# MCU.net
KiCad netlist of a schematic drawn in Altium Designer
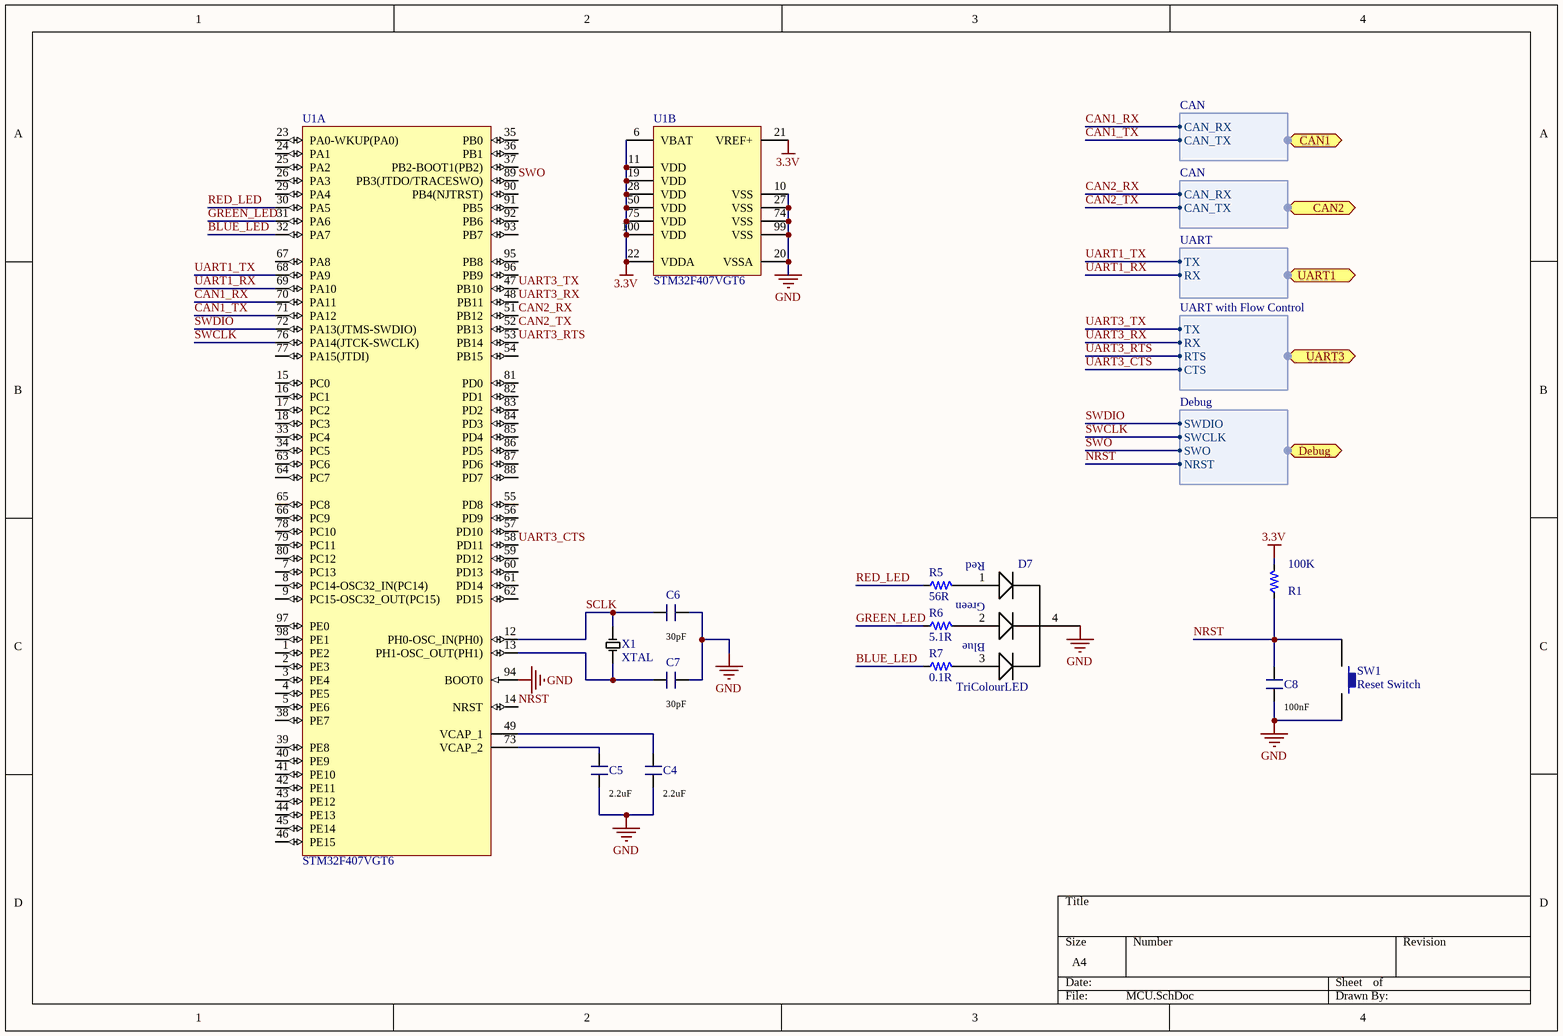
[diagram p0: MCU.SchDoc]

(export (version "E")
  (design (tool "Eeschema 10.0.6"))
  (components
    (comp (ref "C4")
      (value "SCH_GENERIC_CAPACITOR_0603")
      (footprint "PCB_GENERIC_SMD_0603")
      (description "Generic SMD capacitor 0603")
      (fields (field (name "TOLERANCE") "*%") (field (name "CAPACITANCE") "2.2uF"))
      (libsource (lib "Capacitors") (part "SCH_GENERIC_CAPACITOR_0603"))
    )
    (comp (ref "C5")
      (value "SCH_GENERIC_CAPACITOR_0603")
      (footprint "PCB_GENERIC_SMD_0603")
      (description "Generic SMD capacitor 0603")
      (fields (field (name "TOLERANCE") "*%") (field (name "CAPACITANCE") "2.2uF"))
      (libsource (lib "Capacitors") (part "SCH_GENERIC_CAPACITOR_0603"))
    )
    (comp (ref "C6")
      (value "SCH_GENERIC_CAPACITOR_0603")
      (footprint "PCB_GENERIC_SMD_0603")
      (description "Generic SMD capacitor 0603")
      (fields (field (name "TOLERANCE") "*%") (field (name "CAPACITANCE") "30pF"))
      (libsource (lib "Capacitors") (part "SCH_GENERIC_CAPACITOR_0603"))
    )
    (comp (ref "C7")
      (value "SCH_GENERIC_CAPACITOR_0603")
      (footprint "PCB_GENERIC_SMD_0603")
      (description "Generic SMD capacitor 0603")
      (fields (field (name "TOLERANCE") "*%") (field (name "CAPACITANCE") "30pF"))
      (libsource (lib "Capacitors") (part "SCH_GENERIC_CAPACITOR_0603"))
    )
    (comp (ref "C8")
      (value "SCH_GENERIC_CAPACITOR_0603")
      (footprint "PCB_GENERIC_SMD_0603")
      (description "Generic SMD capacitor 0603")
      (fields (field (name "TOLERANCE") "*%") (field (name "CAPACITANCE") "100nF"))
      (libsource (lib "Capacitors") (part "SCH_GENERIC_CAPACITOR_0603"))
    )
    (comp (ref "D7")
      (value "TriColourLED")
      (footprint "TricolourLED - SunLED - DK  1497-1225-2-ND")
      (libsource (lib "TricolourLED - SunLED - DK 1497-1225-2-ND") (part "TriColourLED"))
    )
    (comp (ref "R1")
      (value "SCH_GENERIC_RESISTOR_0603")
      (footprint "PCB_GENERIC_SMD_0603")
      (description "Generic SMD resistor 0603")
      (fields (field (name "RESISTANCE") "100K"))
      (libsource (lib "Resistors") (part "SCH_GENERIC_RESISTOR_0603"))
    )
    (comp (ref "R5")
      (value "SCH_GENERIC_RESISTOR_0603")
      (footprint "PCB_GENERIC_SMD_0603")
      (description "Generic SMD resistor 0603")
      (fields (field (name "RESISTANCE") "56R"))
      (libsource (lib "SCH_GENERIC_RESISTOR_0603") (part "SCH_GENERIC_RESISTOR_0603"))
    )
    (comp (ref "R6")
      (value "SCH_GENERIC_RESISTOR_0603")
      (footprint "PCB_GENERIC_SMD_0603")
      (description "Generic SMD resistor 0603")
      (fields (field (name "RESISTANCE") "5.1R"))
      (libsource (lib "SCH_GENERIC_RESISTOR_0603") (part "SCH_GENERIC_RESISTOR_0603"))
    )
    (comp (ref "R7")
      (value "SCH_GENERIC_RESISTOR_0603")
      (footprint "PCB_GENERIC_SMD_0603")
      (description "Generic SMD resistor 0603")
      (fields (field (name "RESISTANCE") "0.1R"))
      (libsource (lib "SCH_GENERIC_RESISTOR_0603") (part "SCH_GENERIC_RESISTOR_0603"))
    )
    (comp (ref "SW1")
      (value "Reset Switch")
      (footprint "Push Button Switch")
      (libsource (lib "PushButtonSwitch") (part "PushButtonSwitch"))
    )
    (comp (ref "U1")
      (value "STM32F407VGT6")
      (footprint "STM-LQFP100_N")
      (fields (field (name "MANUFACTURER") "STMicroelectronics"))
      (libsource (lib "STMicroelectronics STM32 F4") (part "STM32F407VGT6"))
    )
    (comp (ref "X1") (value "XTAL") (footprint "CRYSTAL_8MHZ") (libsource (lib "Crystal") (part "Crystal")))
  )
  (nets
    (net (code "7") (name "/BLUE_LED") (class "Default")
      (node (ref "R7") (pin "1") (pinfunction "1_1") (pintype "passive"))
      (node (ref "U1") (pin "32") (pinfunction "PA7_32") (pintype "bidirectional"))
    )
    (net (code "8") (name "/CAN1_RX") (class "Default")
      (node (ref "U1") (pin "70") (pinfunction "PA11_70") (pintype "bidirectional"))
    )
    (net (code "9") (name "/CAN1_TX") (class "Default")
      (node (ref "U1") (pin "71") (pinfunction "PA12_71") (pintype "bidirectional"))
    )
    (net (code "10") (name "/CAN2_RX") (class "Default")
      (node (ref "U1") (pin "51") (pinfunction "PB12_51") (pintype "bidirectional"))
    )
    (net (code "11") (name "/CAN2_TX") (class "Default")
      (node (ref "U1") (pin "52") (pinfunction "PB13_52") (pintype "bidirectional"))
    )
    (net (code "12") (name "/GREEN_LED") (class "Default")
      (node (ref "R6") (pin "1") (pinfunction "1_1") (pintype "passive"))
      (node (ref "U1") (pin "31") (pinfunction "PA6_31") (pintype "bidirectional"))
    )
    (net (code "13") (name "/NRST") (class "Default")
      (node (ref "C8") (pin "1") (pinfunction "1_1") (pintype "passive"))
      (node (ref "R1") (pin "1") (pinfunction "1_1") (pintype "passive"))
      (node (ref "SW1") (pin "1") (pinfunction "1_1") (pintype "passive"))
      (node (ref "U1") (pin "14") (pinfunction "NRST_14") (pintype "bidirectional"))
    )
    (net (code "14") (name "/RED_LED") (class "Default")
      (node (ref "R5") (pin "1") (pinfunction "1_1") (pintype "passive"))
      (node (ref "U1") (pin "30") (pinfunction "PA5_30") (pintype "bidirectional"))
    )
    (net (code "15") (name "/SCLK") (class "Default")
      (node (ref "C6") (pin "2") (pinfunction "2_2") (pintype "passive"))
      (node (ref "U1") (pin "12") (pinfunction "PH0-OSC_IN(PH0)_12") (pintype "bidirectional"))
      (node (ref "X1") (pin "1") (pintype "passive"))
    )
    (net (code "16") (name "/SWCLK") (class "Default")
      (node (ref "U1") (pin "76") (pinfunction "PA14(JTCK-SWCLK)_76") (pintype "bidirectional"))
    )
    (net (code "17") (name "/SWDIO") (class "Default")
      (node (ref "U1") (pin "72") (pinfunction "PA13(JTMS-SWDIO)_72") (pintype "bidirectional"))
    )
    (net (code "18") (name "/SWO") (class "Default")
      (node (ref "U1") (pin "89") (pinfunction "PB3(JTDO/TRACESWO)_89") (pintype "bidirectional"))
    )
    (net (code "19") (name "/UART1_RX") (class "Default")
      (node (ref "U1") (pin "69") (pinfunction "PA10_69") (pintype "bidirectional"))
    )
    (net (code "20") (name "/UART1_TX") (class "Default")
      (node (ref "U1") (pin "68") (pinfunction "PA9_68") (pintype "bidirectional"))
    )
    (net (code "21") (name "/UART3_CTS") (class "Default")
      (node (ref "U1") (pin "58") (pinfunction "PD11_58") (pintype "bidirectional"))
    )
    (net (code "22") (name "/UART3_RTS") (class "Default")
      (node (ref "U1") (pin "53") (pinfunction "PB14_53") (pintype "bidirectional"))
    )
    (net (code "23") (name "/UART3_RX") (class "Default")
      (node (ref "U1") (pin "48") (pinfunction "PB11_48") (pintype "bidirectional"))
    )
    (net (code "24") (name "/UART3_TX") (class "Default")
      (node (ref "U1") (pin "47") (pinfunction "PB10_47") (pintype "bidirectional"))
    )
    (net (code "29") (name "3.3V") (class "Default")
      (node (ref "R1") (pin "2") (pinfunction "2_2") (pintype "passive"))
      (node (ref "U1") (pin "100") (pinfunction "VDD_100") (pintype "power_in"))
      (node (ref "U1") (pin "11") (pinfunction "VDD_11") (pintype "power_in"))
      (node (ref "U1") (pin "19") (pinfunction "VDD_19") (pintype "power_in"))
      (node (ref "U1") (pin "21") (pinfunction "VREF+_21") (pintype "power_in"))
      (node (ref "U1") (pin "22") (pinfunction "VDDA_22") (pintype "power_in"))
      (node (ref "U1") (pin "28") (pinfunction "VDD_28") (pintype "power_in"))
      (node (ref "U1") (pin "50") (pinfunction "VDD_50") (pintype "power_in"))
      (node (ref "U1") (pin "6") (pinfunction "VBAT_6") (pintype "power_in"))
      (node (ref "U1") (pin "75") (pinfunction "VDD_75") (pintype "power_in"))
    )
    (net (code "30") (name "GND") (class "Default")
      (node (ref "C4") (pin "1") (pinfunction "1_1") (pintype "passive"))
      (node (ref "C5") (pin "1") (pinfunction "1_1") (pintype "passive"))
      (node (ref "C6") (pin "1") (pinfunction "1_1") (pintype "passive"))
      (node (ref "C7") (pin "1") (pinfunction "1_1") (pintype "passive"))
      (node (ref "C8") (pin "2") (pinfunction "2_2") (pintype "passive"))
      (node (ref "D7") (pin "4") (pinfunction "4_4") (pintype "passive"))
      (node (ref "SW1") (pin "2") (pinfunction "2_2") (pintype "passive"))
      (node (ref "U1") (pin "10") (pinfunction "VSS_10") (pintype "power_in"))
      (node (ref "U1") (pin "20") (pinfunction "VSSA_20") (pintype "power_in"))
      (node (ref "U1") (pin "27") (pinfunction "VSS_27") (pintype "power_in"))
      (node (ref "U1") (pin "74") (pinfunction "VSS_74") (pintype "power_in"))
      (node (ref "U1") (pin "94") (pinfunction "BOOT0_94") (pintype "input"))
      (node (ref "U1") (pin "99") (pinfunction "VSS_99") (pintype "power_in"))
    )
    (net (code "31") (name "Net-(D7-Blue)") (class "Default")
      (node (ref "D7") (pin "3") (pinfunction "Blue_3") (pintype "passive"))
      (node (ref "R7") (pin "2") (pinfunction "2_2") (pintype "passive"))
    )
    (net (code "32") (name "Net-(D7-Green)") (class "Default")
      (node (ref "D7") (pin "2") (pinfunction "Green_2") (pintype "passive"))
      (node (ref "R6") (pin "2") (pinfunction "2_2") (pintype "passive"))
    )
    (net (code "33") (name "Net-(D7-Red)") (class "Default")
      (node (ref "D7") (pin "1") (pinfunction "Red_1") (pintype "passive"))
      (node (ref "R5") (pin "2") (pinfunction "2_2") (pintype "passive"))
    )
    (net (code "34") (name "Net-(U1A-PH1-OSC_OUT(PH1))") (class "Default")
      (node (ref "C7") (pin "2") (pinfunction "2_2") (pintype "passive"))
      (node (ref "U1") (pin "13") (pinfunction "PH1-OSC_OUT(PH1)_13") (pintype "bidirectional"))
      (node (ref "X1") (pin "2") (pintype "passive"))
    )
    (net (code "35") (name "Net-(U1A-VCAP_1)") (class "Default")
      (node (ref "C4") (pin "2") (pinfunction "2_2") (pintype "passive"))
      (node (ref "U1") (pin "49") (pinfunction "VCAP_1_49") (pintype "power_in"))
    )
    (net (code "36") (name "Net-(U1A-VCAP_2)") (class "Default")
      (node (ref "C5") (pin "2") (pinfunction "2_2") (pintype "passive"))
      (node (ref "U1") (pin "73") (pinfunction "VCAP_2_73") (pintype "power_in"))
    )
    (net (code "37") (name "unconnected-(U1A-PA0-WKUP(PA0)-Pad23)") (class "Default")
      (node (ref "U1") (pin "23") (pinfunction "PA0-WKUP(PA0)_23") (pintype "bidirectional"))
    )
    (net (code "38") (name "unconnected-(U1A-PA1-Pad24)") (class "Default")
      (node (ref "U1") (pin "24") (pinfunction "PA1_24") (pintype "bidirectional"))
    )
    (net (code "39") (name "unconnected-(U1A-PA2-Pad25)") (class "Default")
      (node (ref "U1") (pin "25") (pinfunction "PA2_25") (pintype "bidirectional"))
    )
    (net (code "40") (name "unconnected-(U1A-PA3-Pad26)") (class "Default")
      (node (ref "U1") (pin "26") (pinfunction "PA3_26") (pintype "bidirectional"))
    )
    (net (code "41") (name "unconnected-(U1A-PA4-Pad29)") (class "Default")
      (node (ref "U1") (pin "29") (pinfunction "PA4_29") (pintype "bidirectional"))
    )
    (net (code "42") (name "unconnected-(U1A-PA8-Pad67)") (class "Default")
      (node (ref "U1") (pin "67") (pinfunction "PA8_67") (pintype "bidirectional"))
    )
    (net (code "43") (name "unconnected-(U1A-PA15(JTDI)-Pad77)") (class "Default")
      (node (ref "U1") (pin "77") (pinfunction "PA15(JTDI)_77") (pintype "bidirectional"))
    )
    (net (code "44") (name "unconnected-(U1A-PB0-Pad35)") (class "Default")
      (node (ref "U1") (pin "35") (pinfunction "PB0_35") (pintype "bidirectional"))
    )
    (net (code "45") (name "unconnected-(U1A-PB1-Pad36)") (class "Default")
      (node (ref "U1") (pin "36") (pinfunction "PB1_36") (pintype "bidirectional"))
    )
    (net (code "46") (name "unconnected-(U1A-PB2-BOOT1(PB2)-Pad37)") (class "Default")
      (node (ref "U1") (pin "37") (pinfunction "PB2-BOOT1(PB2)_37") (pintype "bidirectional"))
    )
    (net (code "47") (name "unconnected-(U1A-PB4(NJTRST)-Pad90)") (class "Default")
      (node (ref "U1") (pin "90") (pinfunction "PB4(NJTRST)_90") (pintype "bidirectional"))
    )
    (net (code "48") (name "unconnected-(U1A-PB5-Pad91)") (class "Default")
      (node (ref "U1") (pin "91") (pinfunction "PB5_91") (pintype "bidirectional"))
    )
    (net (code "49") (name "unconnected-(U1A-PB6-Pad92)") (class "Default")
      (node (ref "U1") (pin "92") (pinfunction "PB6_92") (pintype "bidirectional"))
    )
    (net (code "50") (name "unconnected-(U1A-PB7-Pad93)") (class "Default")
      (node (ref "U1") (pin "93") (pinfunction "PB7_93") (pintype "bidirectional"))
    )
    (net (code "51") (name "unconnected-(U1A-PB8-Pad95)") (class "Default")
      (node (ref "U1") (pin "95") (pinfunction "PB8_95") (pintype "bidirectional"))
    )
    (net (code "52") (name "unconnected-(U1A-PB9-Pad96)") (class "Default")
      (node (ref "U1") (pin "96") (pinfunction "PB9_96") (pintype "bidirectional"))
    )
    (net (code "53") (name "unconnected-(U1A-PB15-Pad54)") (class "Default")
      (node (ref "U1") (pin "54") (pinfunction "PB15_54") (pintype "bidirectional"))
    )
    (net (code "54") (name "unconnected-(U1A-PC0-Pad15)") (class "Default")
      (node (ref "U1") (pin "15") (pinfunction "PC0_15") (pintype "bidirectional"))
    )
    (net (code "55") (name "unconnected-(U1A-PC1-Pad16)") (class "Default")
      (node (ref "U1") (pin "16") (pinfunction "PC1_16") (pintype "bidirectional"))
    )
    (net (code "56") (name "unconnected-(U1A-PC2-Pad17)") (class "Default")
      (node (ref "U1") (pin "17") (pinfunction "PC2_17") (pintype "bidirectional"))
    )
    (net (code "57") (name "unconnected-(U1A-PC3-Pad18)") (class "Default")
      (node (ref "U1") (pin "18") (pinfunction "PC3_18") (pintype "bidirectional"))
    )
    (net (code "58") (name "unconnected-(U1A-PC4-Pad33)") (class "Default")
      (node (ref "U1") (pin "33") (pinfunction "PC4_33") (pintype "bidirectional"))
    )
    (net (code "59") (name "unconnected-(U1A-PC5-Pad34)") (class "Default")
      (node (ref "U1") (pin "34") (pinfunction "PC5_34") (pintype "bidirectional"))
    )
    (net (code "60") (name "unconnected-(U1A-PC6-Pad63)") (class "Default")
      (node (ref "U1") (pin "63") (pinfunction "PC6_63") (pintype "bidirectional"))
    )
    (net (code "61") (name "unconnected-(U1A-PC7-Pad64)") (class "Default")
      (node (ref "U1") (pin "64") (pinfunction "PC7_64") (pintype "bidirectional"))
    )
    (net (code "62") (name "unconnected-(U1A-PC8-Pad65)") (class "Default")
      (node (ref "U1") (pin "65") (pinfunction "PC8_65") (pintype "bidirectional"))
    )
    (net (code "63") (name "unconnected-(U1A-PC9-Pad66)") (class "Default")
      (node (ref "U1") (pin "66") (pinfunction "PC9_66") (pintype "bidirectional"))
    )
    (net (code "64") (name "unconnected-(U1A-PC10-Pad78)") (class "Default")
      (node (ref "U1") (pin "78") (pinfunction "PC10_78") (pintype "bidirectional"))
    )
    (net (code "65") (name "unconnected-(U1A-PC11-Pad79)") (class "Default")
      (node (ref "U1") (pin "79") (pinfunction "PC11_79") (pintype "bidirectional"))
    )
    (net (code "66") (name "unconnected-(U1A-PC12-Pad80)") (class "Default")
      (node (ref "U1") (pin "80") (pinfunction "PC12_80") (pintype "bidirectional"))
    )
    (net (code "67") (name "unconnected-(U1A-PC13-Pad7)") (class "Default")
      (node (ref "U1") (pin "7") (pinfunction "PC13_7") (pintype "bidirectional"))
    )
    (net (code "68") (name "unconnected-(U1A-PC14-OSC32_IN(PC14)-Pad8)") (class "Default")
      (node (ref "U1") (pin "8") (pinfunction "PC14-OSC32_IN(PC14)_8") (pintype "bidirectional"))
    )
    (net (code "69") (name "unconnected-(U1A-PC15-OSC32_OUT(PC15)-Pad9)") (class "Default")
      (node (ref "U1") (pin "9") (pinfunction "PC15-OSC32_OUT(PC15)_9") (pintype "bidirectional"))
    )
    (net (code "70") (name "unconnected-(U1A-PD0-Pad81)") (class "Default")
      (node (ref "U1") (pin "81") (pinfunction "PD0_81") (pintype "bidirectional"))
    )
    (net (code "71") (name "unconnected-(U1A-PD1-Pad82)") (class "Default")
      (node (ref "U1") (pin "82") (pinfunction "PD1_82") (pintype "bidirectional"))
    )
    (net (code "72") (name "unconnected-(U1A-PD2-Pad83)") (class "Default")
      (node (ref "U1") (pin "83") (pinfunction "PD2_83") (pintype "bidirectional"))
    )
    (net (code "73") (name "unconnected-(U1A-PD3-Pad84)") (class "Default")
      (node (ref "U1") (pin "84") (pinfunction "PD3_84") (pintype "bidirectional"))
    )
    (net (code "74") (name "unconnected-(U1A-PD4-Pad85)") (class "Default")
      (node (ref "U1") (pin "85") (pinfunction "PD4_85") (pintype "bidirectional"))
    )
    (net (code "75") (name "unconnected-(U1A-PD5-Pad86)") (class "Default")
      (node (ref "U1") (pin "86") (pinfunction "PD5_86") (pintype "bidirectional"))
    )
    (net (code "76") (name "unconnected-(U1A-PD6-Pad87)") (class "Default")
      (node (ref "U1") (pin "87") (pinfunction "PD6_87") (pintype "bidirectional"))
    )
    (net (code "77") (name "unconnected-(U1A-PD7-Pad88)") (class "Default")
      (node (ref "U1") (pin "88") (pinfunction "PD7_88") (pintype "bidirectional"))
    )
    (net (code "78") (name "unconnected-(U1A-PD8-Pad55)") (class "Default")
      (node (ref "U1") (pin "55") (pinfunction "PD8_55") (pintype "bidirectional"))
    )
    (net (code "79") (name "unconnected-(U1A-PD9-Pad56)") (class "Default")
      (node (ref "U1") (pin "56") (pinfunction "PD9_56") (pintype "bidirectional"))
    )
    (net (code "80") (name "unconnected-(U1A-PD10-Pad57)") (class "Default")
      (node (ref "U1") (pin "57") (pinfunction "PD10_57") (pintype "bidirectional"))
    )
    (net (code "81") (name "unconnected-(U1A-PD12-Pad59)") (class "Default")
      (node (ref "U1") (pin "59") (pinfunction "PD12_59") (pintype "bidirectional"))
    )
    (net (code "82") (name "unconnected-(U1A-PD13-Pad60)") (class "Default")
      (node (ref "U1") (pin "60") (pinfunction "PD13_60") (pintype "bidirectional"))
    )
    (net (code "83") (name "unconnected-(U1A-PD14-Pad61)") (class "Default")
      (node (ref "U1") (pin "61") (pinfunction "PD14_61") (pintype "bidirectional"))
    )
    (net (code "84") (name "unconnected-(U1A-PD15-Pad62)") (class "Default")
      (node (ref "U1") (pin "62") (pinfunction "PD15_62") (pintype "bidirectional"))
    )
    (net (code "85") (name "unconnected-(U1A-PE0-Pad97)") (class "Default")
      (node (ref "U1") (pin "97") (pinfunction "PE0_97") (pintype "bidirectional"))
    )
    (net (code "86") (name "unconnected-(U1A-PE1-Pad98)") (class "Default")
      (node (ref "U1") (pin "98") (pinfunction "PE1_98") (pintype "bidirectional"))
    )
    (net (code "87") (name "unconnected-(U1A-PE2-Pad1)") (class "Default")
      (node (ref "U1") (pin "1") (pinfunction "PE2_1") (pintype "bidirectional"))
    )
    (net (code "88") (name "unconnected-(U1A-PE3-Pad2)") (class "Default")
      (node (ref "U1") (pin "2") (pinfunction "PE3_2") (pintype "bidirectional"))
    )
    (net (code "89") (name "unconnected-(U1A-PE4-Pad3)") (class "Default")
      (node (ref "U1") (pin "3") (pinfunction "PE4_3") (pintype "bidirectional"))
    )
    (net (code "90") (name "unconnected-(U1A-PE5-Pad4)") (class "Default")
      (node (ref "U1") (pin "4") (pinfunction "PE5_4") (pintype "bidirectional"))
    )
    (net (code "91") (name "unconnected-(U1A-PE6-Pad5)") (class "Default")
      (node (ref "U1") (pin "5") (pinfunction "PE6_5") (pintype "bidirectional"))
    )
    (net (code "92") (name "unconnected-(U1A-PE7-Pad38)") (class "Default")
      (node (ref "U1") (pin "38") (pinfunction "PE7_38") (pintype "bidirectional"))
    )
    (net (code "93") (name "unconnected-(U1A-PE8-Pad39)") (class "Default")
      (node (ref "U1") (pin "39") (pinfunction "PE8_39") (pintype "bidirectional"))
    )
    (net (code "94") (name "unconnected-(U1A-PE9-Pad40)") (class "Default")
      (node (ref "U1") (pin "40") (pinfunction "PE9_40") (pintype "bidirectional"))
    )
    (net (code "95") (name "unconnected-(U1A-PE10-Pad41)") (class "Default")
      (node (ref "U1") (pin "41") (pinfunction "PE10_41") (pintype "bidirectional"))
    )
    (net (code "96") (name "unconnected-(U1A-PE11-Pad42)") (class "Default")
      (node (ref "U1") (pin "42") (pinfunction "PE11_42") (pintype "bidirectional"))
    )
    (net (code "97") (name "unconnected-(U1A-PE12-Pad43)") (class "Default")
      (node (ref "U1") (pin "43") (pinfunction "PE12_43") (pintype "bidirectional"))
    )
    (net (code "98") (name "unconnected-(U1A-PE13-Pad44)") (class "Default")
      (node (ref "U1") (pin "44") (pinfunction "PE13_44") (pintype "bidirectional"))
    )
    (net (code "99") (name "unconnected-(U1A-PE14-Pad45)") (class "Default")
      (node (ref "U1") (pin "45") (pinfunction "PE14_45") (pintype "bidirectional"))
    )
    (net (code "100") (name "unconnected-(U1A-PE15-Pad46)") (class "Default")
      (node (ref "U1") (pin "46") (pinfunction "PE15_46") (pintype "bidirectional"))
    )
  )
)
